# rapidshark-half-assed-full-h-bridge-mk-1.net
KiCad netlist of a schematic drawn in EAGLE
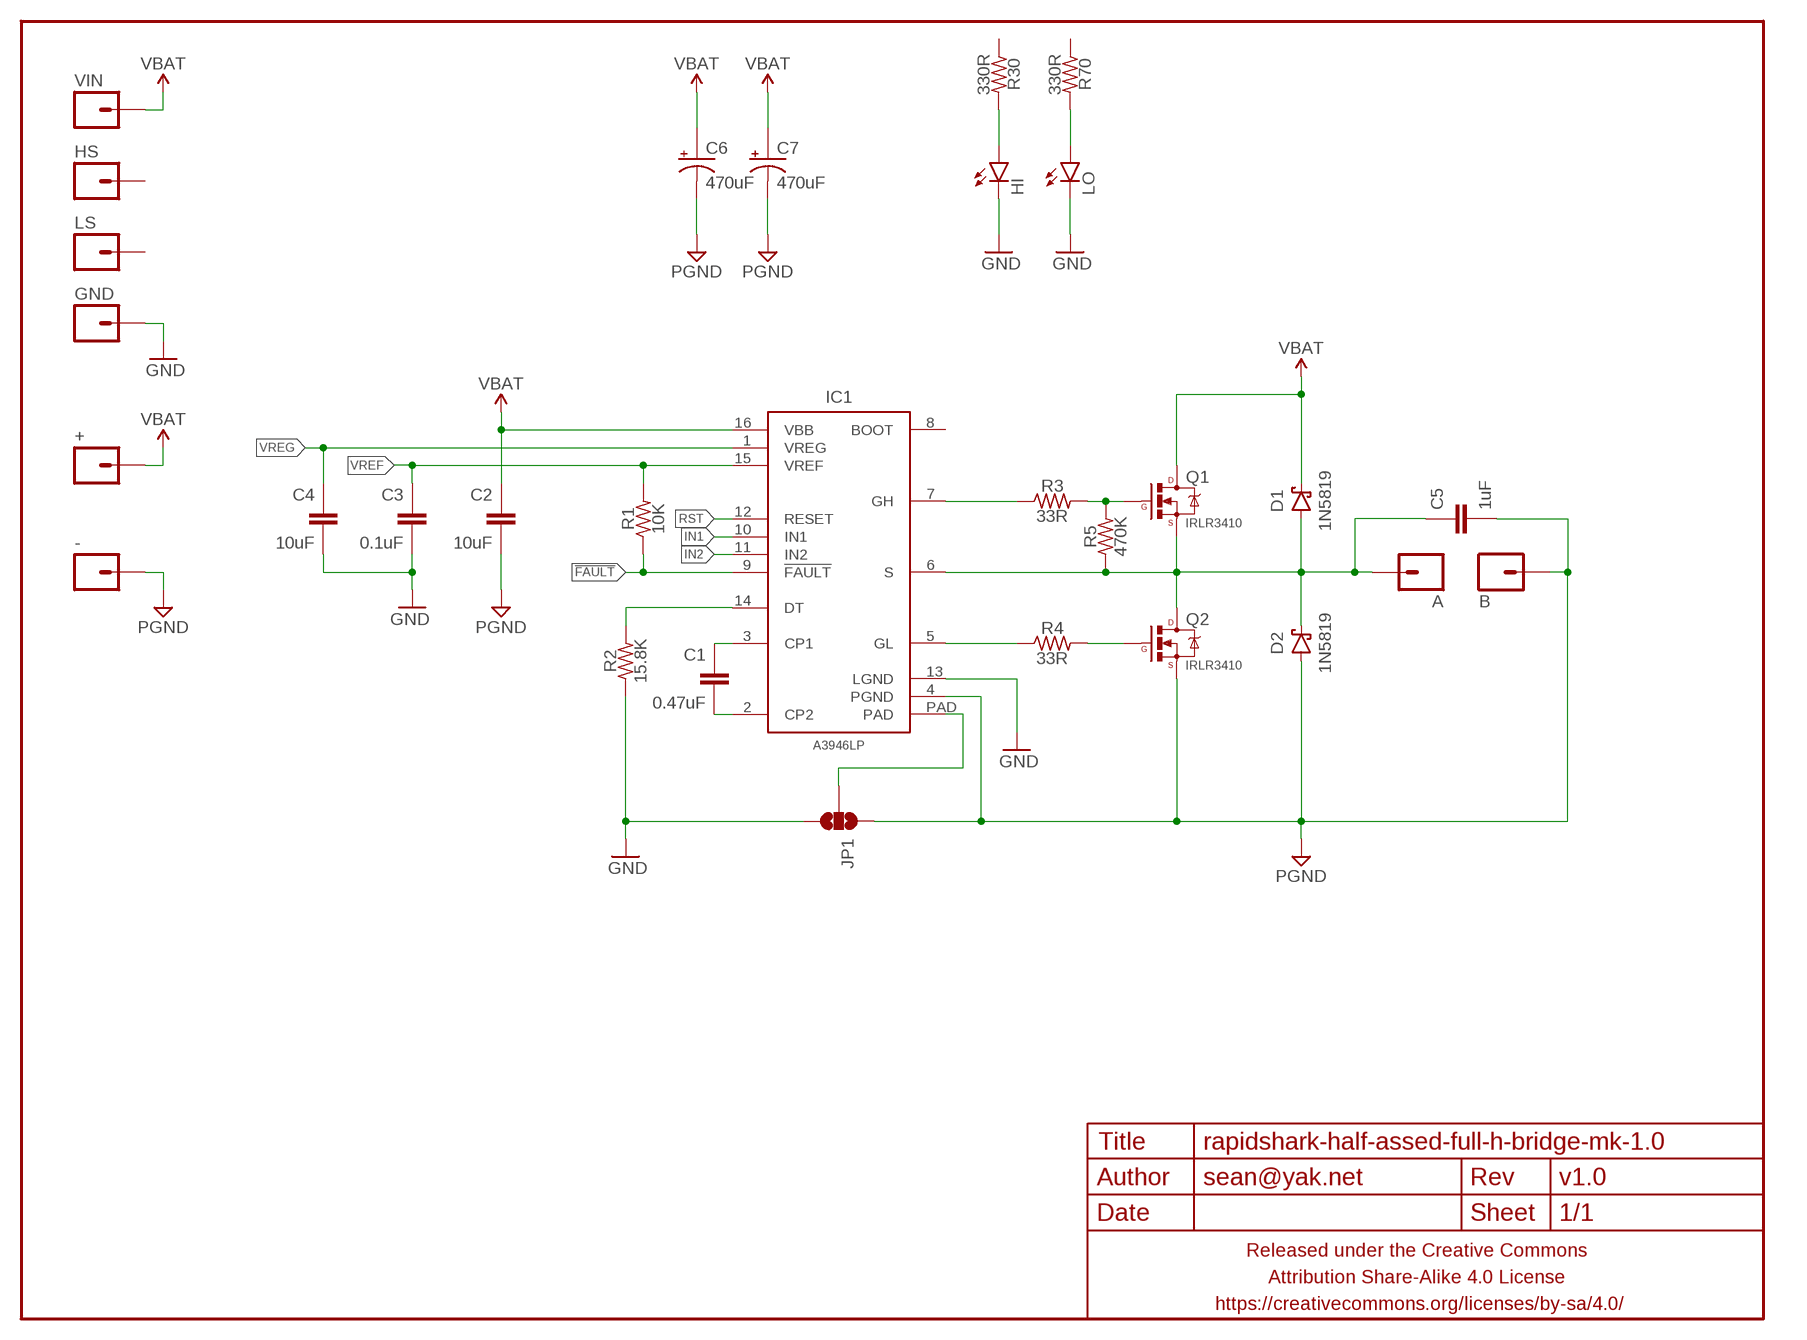
[diagram p0: schematic, sheet 1]

(export (version "E")
  (design (tool "Eeschema 10.0.6"))
  (components
    (comp (ref "+")
      (value "M01PTH-1.9MM")
      (footprint "eagle-import:1X01-1.9MM-CIR")
      (libsource (lib "eagle-import") (part "M01PTH-1.9MM"))
    )
    (comp (ref "-")
      (value "M01PTH-1.9MM")
      (footprint "eagle-import:1X01-1.9MM-CIR")
      (libsource (lib "eagle-import") (part "M01PTH-1.9MM"))
    )
    (comp (ref "A")
      (value "M01PTH-1.9MM")
      (footprint "eagle-import:1X01-1.9MM-CIR")
      (libsource (lib "eagle-import") (part "M01PTH-1.9MM"))
    )
    (comp (ref "B")
      (value "M01PTH-1.9MM")
      (footprint "eagle-import:1X01-1.9MM-CIR")
      (libsource (lib "eagle-import") (part "M01PTH-1.9MM"))
    )
    (comp (ref "C1")
      (value "0.47uF")
      (footprint "eagle-import:C0603-TIGHTER")
      (libsource (lib "eagle-import") (part "CAPACITOR-CERAMICC0603-TIGHTER"))
    )
    (comp (ref "C2")
      (value "10uF")
      (footprint "eagle-import:C0805-TIGHTER")
      (libsource (lib "eagle-import") (part "CAPACITOR-CERAMICC0805-TIGHTER"))
    )
    (comp (ref "C3")
      (value "0.1uF")
      (footprint "eagle-import:C0603-TIGHTER")
      (libsource (lib "eagle-import") (part "CAPACITOR-CERAMICC0603-TIGHTER"))
    )
    (comp (ref "C4")
      (value "10uF")
      (footprint "eagle-import:C0805-TIGHTER")
      (libsource (lib "eagle-import") (part "CAPACITOR-CERAMICC0805-TIGHTER"))
    )
    (comp (ref "C5")
      (value "1uF")
      (footprint "eagle-import:C0603-TIGHTER")
      (libsource (lib "eagle-import") (part "CAPACITOR-CERAMICC0603-TIGHTER"))
    )
    (comp (ref "C6")
      (value "470uF")
      (footprint "eagle-import:E5-10,5")
      (libsource (lib "eagle-import") (part "CAPACITOR-POLARIZEDE5-10.5"))
    )
    (comp (ref "C7")
      (value "470uF")
      (footprint "eagle-import:E5-10,5")
      (libsource (lib "eagle-import") (part "CAPACITOR-POLARIZEDE5-10.5"))
    )
    (comp (ref "D1")
      (value "1N5819")
      (footprint "eagle-import:SMA-DIODE-SCHOTTKY")
      (libsource (lib "eagle-import") (part "DIODE-SCHOTTKYSMA"))
    )
    (comp (ref "D2")
      (value "1N5819")
      (footprint "eagle-import:SMA-DIODE-SCHOTTKY")
      (libsource (lib "eagle-import") (part "DIODE-SCHOTTKYSMA"))
    )
    (comp (ref "FRAME1")
      (value "FRAME-LETTERNO_PACKAGE")
      (footprint "eagle-import:DUMMY")
      (fields (field (name "DESIGNER") "sean@yak.net") (field (name "VERSION") "v1.0"))
      (libsource (lib "eagle-import") (part "FRAME-LETTERNO_PACKAGE"))
    )
    (comp (ref "GND")
      (value "M01PTH")
      (footprint "eagle-import:1X01")
      (libsource (lib "eagle-import") (part "M01PTH"))
    )
    (comp (ref "HI")
      (value "LED0603-TIGHT")
      (footprint "eagle-import:LED-0603-TIGHT")
      (libsource (lib "eagle-import") (part "LED0603-TIGHT"))
    )
    (comp (ref "HS")
      (value "M01PTH")
      (footprint "eagle-import:1X01")
      (libsource (lib "eagle-import") (part "M01PTH"))
    )
    (comp (ref "IC1")
      (value "A3946LP")
      (footprint "eagle-import:TSSOP-16-PAD")
      (libsource (lib "eagle-import") (part "A3946LP"))
    )
    (comp (ref "JP1")
      (value "JUMPER-PAD-3-NOFULL_BOX_SILK")
      (footprint "eagle-import:PAD-JUMPER-3-NO_YES_SILK_FULL_BOX")
      (libsource (lib "eagle-import") (part "JUMPER-PAD-3-NOFULL_BOX_SILK"))
    )
    (comp (ref "LO")
      (value "LED0603-TIGHT")
      (footprint "eagle-import:LED-0603-TIGHT")
      (libsource (lib "eagle-import") (part "LED0603-TIGHT"))
    )
    (comp (ref "LS")
      (value "M01PTH")
      (footprint "eagle-import:1X01")
      (libsource (lib "eagle-import") (part "M01PTH"))
    )
    (comp (ref "Q1")
      (value "IRLR3410")
      (footprint "eagle-import:DPAK")
      (libsource (lib "eagle-import") (part "MOSFET-NCHANNELFDD8780"))
    )
    (comp (ref "Q2")
      (value "IRLR3410")
      (footprint "eagle-import:DPAK")
      (libsource (lib "eagle-import") (part "MOSFET-NCHANNELFDD8780"))
    )
    (comp (ref "R1")
      (value "10K")
      (footprint "eagle-import:R0603-TIGHTER")
      (libsource (lib "eagle-import") (part "RESISTORR0603-TIGHTER"))
    )
    (comp (ref "R2")
      (value "15.8K")
      (footprint "eagle-import:R0603-TIGHTER")
      (libsource (lib "eagle-import") (part "RESISTORR0603-TIGHTER"))
    )
    (comp (ref "R3")
      (value "33R")
      (footprint "eagle-import:R0603-TIGHTER")
      (libsource (lib "eagle-import") (part "RESISTORR0603-TIGHTER"))
    )
    (comp (ref "R4")
      (value "33R")
      (footprint "eagle-import:R0603-TIGHTER")
      (libsource (lib "eagle-import") (part "RESISTORR0603-TIGHTER"))
    )
    (comp (ref "R5")
      (value "470K")
      (footprint "eagle-import:R0603-TIGHTER")
      (libsource (lib "eagle-import") (part "RESISTORR0603-TIGHTER"))
    )
    (comp (ref "R30")
      (value "330R")
      (footprint "eagle-import:R0603-TIGHTER")
      (libsource (lib "eagle-import") (part "RESISTORR0603-TIGHTER"))
    )
    (comp (ref "R70")
      (value "330R")
      (footprint "eagle-import:R0603-TIGHTER")
      (libsource (lib "eagle-import") (part "RESISTORR0603-TIGHTER"))
    )
    (comp (ref "VIN")
      (value "M01PTH")
      (footprint "eagle-import:1X01")
      (libsource (lib "eagle-import") (part "M01PTH"))
    )
  )
  (nets
    (net (code "1") (name "/~{FAULT}") (class "Default")
      (node (ref "IC1") (pin "9") (pinfunction "~{FAULT}_9") (pintype "bidirectional"))
      (node (ref "R1") (pin "1") (pinfunction "1_1") (pintype "passive"))
    )
    (net (code "2") (name "GND") (class "Default")
      (node (ref "C3") (pin "2") (pinfunction "2_2") (pintype "passive"))
      (node (ref "C4") (pin "2") (pinfunction "2_2") (pintype "passive"))
      (node (ref "GND") (pin "1") (pinfunction "1_1") (pintype "passive"))
      (node (ref "HI") (pin "C") (pinfunction "C_C") (pintype "passive"))
      (node (ref "IC1") (pin "13") (pinfunction "LGND_13") (pintype "bidirectional"))
      (node (ref "JP1") (pin "3") (pinfunction "3_3") (pintype "passive"))
      (node (ref "LO") (pin "C") (pinfunction "C_C") (pintype "passive"))
      (node (ref "R2") (pin "1") (pinfunction "1_1") (pintype "passive"))
    )
    (net (code "3") (name "IN1") (class "Default")
      (node (ref "IC1") (pin "10") (pinfunction "IN1_10") (pintype "bidirectional"))
    )
    (net (code "4") (name "IN2") (class "Default")
      (node (ref "IC1") (pin "11") (pinfunction "IN2_11") (pintype "bidirectional"))
    )
    (net (code "5") (name "Net-(A-1)") (class "Default")
      (node (ref "A") (pin "P$1") (pinfunction "1_P$1") (pintype "passive"))
      (node (ref "C5") (pin "1") (pinfunction "1_1") (pintype "passive"))
      (node (ref "D1") (pin "A") (pinfunction "A_A") (pintype "passive"))
      (node (ref "D2") (pin "C") (pinfunction "C_C") (pintype "passive"))
      (node (ref "IC1") (pin "6") (pinfunction "S_6") (pintype "bidirectional"))
      (node (ref "Q1") (pin "3") (pinfunction "S_3") (pintype "passive"))
      (node (ref "Q2") (pin "4") (pinfunction "D_4") (pintype "passive"))
      (node (ref "R5") (pin "1") (pinfunction "1_1") (pintype "passive"))
    )
    (net (code "6") (name "Net-(HI-PadA)") (class "Default")
      (node (ref "HI") (pin "A") (pinfunction "A_A") (pintype "passive"))
      (node (ref "R30") (pin "2") (pinfunction "2_2") (pintype "passive"))
    )
    (net (code "7") (name "Net-(IC1-CP1)") (class "Default")
      (node (ref "C1") (pin "1") (pinfunction "1_1") (pintype "passive"))
      (node (ref "IC1") (pin "3") (pinfunction "CP1_3") (pintype "bidirectional"))
    )
    (net (code "8") (name "Net-(IC1-CP2)") (class "Default")
      (node (ref "C1") (pin "2") (pinfunction "2_2") (pintype "passive"))
      (node (ref "IC1") (pin "2") (pinfunction "CP2_2") (pintype "bidirectional"))
    )
    (net (code "9") (name "Net-(IC1-DT)") (class "Default")
      (node (ref "IC1") (pin "14") (pinfunction "DT_14") (pintype "bidirectional"))
      (node (ref "R2") (pin "2") (pinfunction "2_2") (pintype "passive"))
    )
    (net (code "10") (name "Net-(IC1-GH)") (class "Default")
      (node (ref "IC1") (pin "7") (pinfunction "GH_7") (pintype "bidirectional"))
      (node (ref "R3") (pin "1") (pinfunction "1_1") (pintype "passive"))
    )
    (net (code "11") (name "Net-(IC1-GL)") (class "Default")
      (node (ref "IC1") (pin "5") (pinfunction "GL_5") (pintype "bidirectional"))
      (node (ref "R4") (pin "1") (pinfunction "1_1") (pintype "passive"))
    )
    (net (code "12") (name "Net-(IC1-PadPAD)") (class "Default")
      (node (ref "IC1") (pin "PAD") (pinfunction "PAD_PAD") (pintype "bidirectional"))
      (node (ref "JP1") (pin "2") (pinfunction "2_2") (pintype "passive"))
    )
    (net (code "13") (name "Net-(LO-PadA)") (class "Default")
      (node (ref "LO") (pin "A") (pinfunction "A_A") (pintype "passive"))
      (node (ref "R70") (pin "2") (pinfunction "2_2") (pintype "passive"))
    )
    (net (code "14") (name "Net-(Q1-G)") (class "Default")
      (node (ref "Q1") (pin "1") (pinfunction "G_1") (pintype "passive"))
      (node (ref "R3") (pin "2") (pinfunction "2_2") (pintype "passive"))
      (node (ref "R5") (pin "2") (pinfunction "2_2") (pintype "passive"))
    )
    (net (code "15") (name "Net-(Q2-G)") (class "Default")
      (node (ref "Q2") (pin "1") (pinfunction "G_1") (pintype "passive"))
      (node (ref "R4") (pin "2") (pinfunction "2_2") (pintype "passive"))
    )
    (net (code "16") (name "PGND") (class "Default")
      (node (ref "-") (pin "P$1") (pinfunction "1_P$1") (pintype "passive"))
      (node (ref "B") (pin "P$1") (pinfunction "1_P$1") (pintype "passive"))
      (node (ref "C2") (pin "2") (pinfunction "2_2") (pintype "passive"))
      (node (ref "C5") (pin "2") (pinfunction "2_2") (pintype "passive"))
      (node (ref "C6") (pin "-") (pinfunction "-_-") (pintype "passive"))
      (node (ref "C7") (pin "-") (pinfunction "-_-") (pintype "passive"))
      (node (ref "D2") (pin "A") (pinfunction "A_A") (pintype "passive"))
      (node (ref "IC1") (pin "4") (pinfunction "PGND_4") (pintype "bidirectional"))
      (node (ref "JP1") (pin "1") (pinfunction "1_1") (pintype "passive"))
      (node (ref "Q2") (pin "3") (pinfunction "S_3") (pintype "passive"))
    )
    (net (code "17") (name "RST") (class "Default")
      (node (ref "IC1") (pin "12") (pinfunction "RESET_12") (pintype "bidirectional"))
    )
    (net (code "18") (name "VBAT") (class "Default")
      (node (ref "+") (pin "P$1") (pinfunction "1_P$1") (pintype "passive"))
      (node (ref "C2") (pin "1") (pinfunction "1_1") (pintype "passive"))
      (node (ref "C6") (pin "+") (pinfunction "+_+") (pintype "passive"))
      (node (ref "C7") (pin "+") (pinfunction "+_+") (pintype "passive"))
      (node (ref "D1") (pin "C") (pinfunction "C_C") (pintype "passive"))
      (node (ref "IC1") (pin "16") (pinfunction "VBB_16") (pintype "bidirectional"))
      (node (ref "Q1") (pin "4") (pinfunction "D_4") (pintype "passive"))
      (node (ref "VIN") (pin "1") (pinfunction "1_1") (pintype "passive"))
    )
    (net (code "19") (name "VREF") (class "Default")
      (node (ref "C3") (pin "1") (pinfunction "1_1") (pintype "passive"))
      (node (ref "IC1") (pin "15") (pinfunction "VREF_15") (pintype "bidirectional"))
      (node (ref "R1") (pin "2") (pinfunction "2_2") (pintype "passive"))
    )
    (net (code "20") (name "VREG") (class "Default")
      (node (ref "C4") (pin "1") (pinfunction "1_1") (pintype "passive"))
      (node (ref "IC1") (pin "1") (pinfunction "VREG_1") (pintype "bidirectional"))
    )
    (net (code "21") (name "unconnected-(HS-Pad1)") (class "Default")
      (node (ref "HS") (pin "1") (pinfunction "1_1") (pintype "passive"))
    )
    (net (code "22") (name "unconnected-(IC1-BOOT-Pad8)") (class "Default")
      (node (ref "IC1") (pin "8") (pinfunction "BOOT_8") (pintype "bidirectional"))
    )
    (net (code "23") (name "unconnected-(LS-Pad1)") (class "Default")
      (node (ref "LS") (pin "1") (pinfunction "1_1") (pintype "passive"))
    )
    (net (code "24") (name "unconnected-(R30-Pad1)") (class "Default")
      (node (ref "R30") (pin "1") (pinfunction "1_1") (pintype "passive"))
    )
    (net (code "25") (name "unconnected-(R70-Pad1)") (class "Default")
      (node (ref "R70") (pin "1") (pinfunction "1_1") (pintype "passive"))
    )
  )
)
